# main.net
KiCad netlist of a schematic drawn in Altium Designer
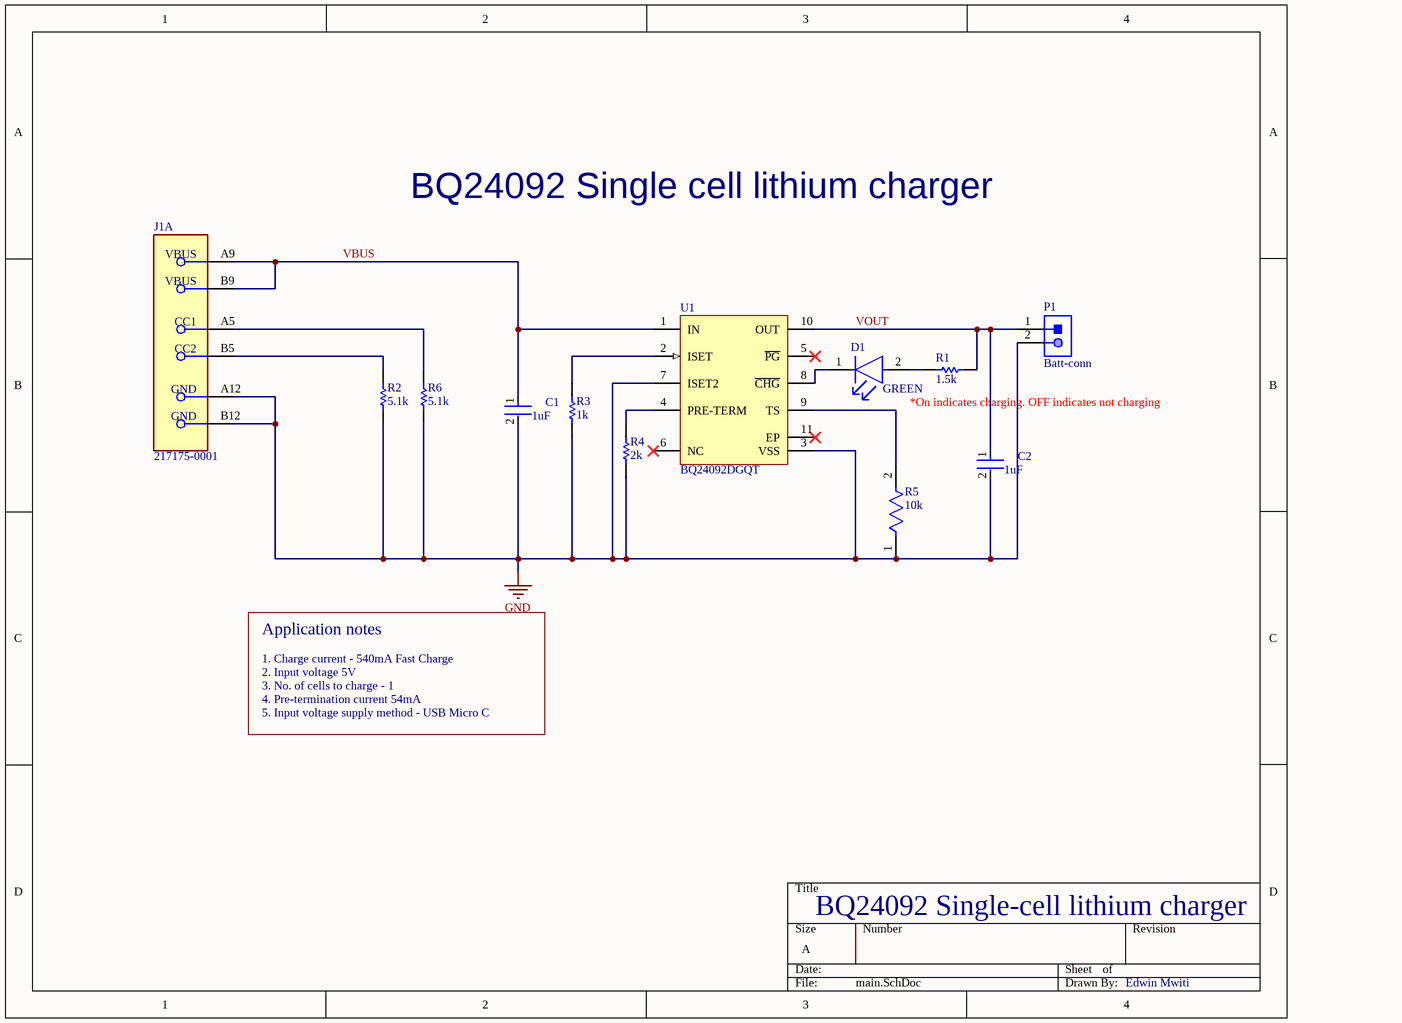
[diagram p0: main.SchDoc]

(export (version "E")
  (design (tool "Eeschema 10.0.6"))
  (components
    (comp (ref "C1")
      (value "1uF")
      (footprint "FP-CC0805-0_85-MFG")
      (description "CAP CER 1UF 16V X7R 0805")
      (fields
        (field (name "MANUFACTURER") "Yageo")
        (field (name "OCTOPART") "https://octopart.com/cc0805kkx7r7bb105-yageo-8376555")
      )
      (libsource (lib "Altium Content Vault") (part "11868f565c42a9108669ba33697ecf6"))
    )
    (comp (ref "C2")
      (value "1uF")
      (footprint "FP-CC0805-0_85-MFG")
      (description "CAP CER 1UF 16V X7R 0805")
      (fields
        (field (name "MANUFACTURER") "Yageo")
        (field (name "OCTOPART") "https://octopart.com/cc0805kkx7r7bb105-yageo-8376555")
      )
      (libsource (lib "Altium Content Vault") (part "11868f565c42a9108669ba33697ecf6"))
    )
    (comp (ref "D1")
      (value "GREEN")
      (footprint "FP-SML-210-MFG")
      (description "LED GREEN CLEAR 0805 SMD")
      (fields (field (name "MANUFACTURER PART NUMBER") "SML-210MTT86") (field (name "MANUFACTURER") "ROHM"))
      (libsource (lib "Altium Content Vault") (part "8706943c75ba83719d021d2fdc84c58"))
    )
    (comp (ref "J1")
      (value "217175-0001")
      (footprint "FP-217175-0001-MFG")
      (description "CONN RCP USB2.0 C 6+18P SMD RA")
      (libsource (lib "Altium Content Vault") (part "6a66c69350f09309f94811689c98437"))
    )
    (comp (ref "P1")
      (value "Batt-conn")
      (footprint "JST-S2B-PH-K-S_V")
      (fields (field (name "TOLERANCE") "20%"))
      (libsource (lib "Altium Content Vault") (part "CN-1P-M-R2"))
    )
    (comp (ref "R1")
      (value "1.5k")
      (footprint "RESC2013X60X40ML20T25")
      (fields (field (name "MANUFACTURER") "Panasonic") (field (name "PART NUMBER") "ERA6AEB152V"))
      (libsource (lib "Altium Content Vault") (part "RES"))
    )
    (comp (ref "R2")
      (value "5.1k")
      (footprint "RESC2013X70X40LL20T20")
      (fields (field (name "MANUFACTURER") "Panasonic") (field (name "PART NUMBER") "ERJ-6GEYJ512V"))
      (libsource (lib "Altium Content Vault") (part "RES"))
    )
    (comp (ref "R3")
      (value "1k")
      (footprint "RESC2013X70X40ML20T20")
      (description "Chip Resistor, 1 KOhm, +/- 1%, 0.125 W, -55 to 155 degC, 0805 (2012 Metric), RoHS, Tape and Reel")
      (fields (field (name "MANUFACTURER") "Panasonic"))
      (libsource (lib "Altium Content Vault") (part "RES-2"))
    )
    (comp (ref "R4")
      (value "2k")
      (footprint "RESC2013X60X35LL10T20")
      (fields (field (name "MANUFACTURER") "Yageo") (field (name "PART NUMBER") "RC0805JR-072KL"))
      (libsource (lib "Altium Content Vault") (part "RES"))
    )
    (comp (ref "R5")
      (value "10k")
      (footprint "FP-CRCW0805-e3-IPC_A")
      (description "RES Thick Film, 10kΩ, 1%, 0.125W, 100ppm/°C, 0805")
      (fields (field (name "TOLERANCE") "1%"))
      (libsource (lib "Altium Content Vault") (part "1029c3af85768c4190bb7ad29bc67b5"))
    )
    (comp (ref "R6")
      (value "5.1k")
      (footprint "RESC2013X70X40LL20T20")
      (fields (field (name "MANUFACTURER") "Panasonic") (field (name "PART NUMBER") "ERJ-6GEYJ512V"))
      (libsource (lib "Altium Content Vault") (part "RES"))
    )
    (comp (ref "U1")
      (value "BQ24092DGQT")
      (footprint "DGQ0010D_M")
      (fields (field (name "MANUFACTURER") "Texas Instruments"))
      (libsource (lib "Altium Content Vault") (part "TI-BQ24092DGQ10-1675X1445TP"))
    )
  )
  (nets
    (net (code "1") (name "/VBUS") (class "Default")
      (node (ref "C1") (pin "1") (pinfunction "1_1") (pintype "passive"))
      (node (ref "J1") (pin "A9") (pinfunction "VBUS_A9") (pintype "power_in"))
      (node (ref "J1") (pin "B9") (pinfunction "VBUS_B9") (pintype "power_in"))
      (node (ref "U1") (pin "1") (pinfunction "IN_1") (pintype "power_in"))
    )
    (net (code "2") (name "/VOUT") (class "Default")
      (node (ref "C2") (pin "1") (pinfunction "1_1") (pintype "passive"))
      (node (ref "P1") (pin "1") (pinfunction "1_1") (pintype "passive"))
      (node (ref "R1") (pin "1") (pinfunction "1_1") (pintype "passive"))
      (node (ref "U1") (pin "10") (pinfunction "OUT_10") (pintype "power_in"))
    )
    (net (code "3") (name "GND") (class "Default")
      (node (ref "C1") (pin "2") (pinfunction "2_2") (pintype "passive"))
      (node (ref "C2") (pin "2") (pinfunction "2_2") (pintype "passive"))
      (node (ref "J1") (pin "A12") (pinfunction "GND_A12") (pintype "power_in"))
      (node (ref "J1") (pin "B12") (pinfunction "GND_B12") (pintype "power_in"))
      (node (ref "P1") (pin "2") (pinfunction "2_2") (pintype "passive"))
      (node (ref "R2") (pin "1") (pinfunction "1_1") (pintype "passive"))
      (node (ref "R3") (pin "1") (pinfunction "1_1") (pintype "passive"))
      (node (ref "R4") (pin "1") (pinfunction "1_1") (pintype "passive"))
      (node (ref "R5") (pin "1") (pinfunction "1_1") (pintype "passive"))
      (node (ref "R6") (pin "1") (pinfunction "1_1") (pintype "passive"))
      (node (ref "U1") (pin "3") (pinfunction "VSS_3") (pintype "power_in"))
      (node (ref "U1") (pin "7") (pinfunction "ISET2_7") (pintype "passive"))
    )
    (net (code "4") (name "Net-(D1-A)") (class "Default")
      (node (ref "D1") (pin "2") (pinfunction "A_2") (pintype "passive"))
      (node (ref "R1") (pin "2") (pinfunction "2_2") (pintype "passive"))
    )
    (net (code "5") (name "Net-(D1-C)") (class "Default")
      (node (ref "D1") (pin "1") (pinfunction "C_1") (pintype "passive"))
      (node (ref "U1") (pin "8") (pinfunction "~{CHG}_8") (pintype "tri_state"))
    )
    (net (code "6") (name "Net-(J1A-CC1)") (class "Default")
      (node (ref "J1") (pin "A5") (pinfunction "CC1_A5") (pintype "passive"))
      (node (ref "R6") (pin "2") (pinfunction "2_2") (pintype "passive"))
    )
    (net (code "7") (name "Net-(J1A-CC2)") (class "Default")
      (node (ref "J1") (pin "B5") (pinfunction "CC2_B5") (pintype "passive"))
      (node (ref "R2") (pin "2") (pinfunction "2_2") (pintype "passive"))
    )
    (net (code "8") (name "Net-(U1-ISET)") (class "Default")
      (node (ref "R3") (pin "2") (pinfunction "2_2") (pintype "passive"))
      (node (ref "U1") (pin "2") (pinfunction "ISET_2") (pintype "input"))
    )
    (net (code "9") (name "Net-(U1-PRE-TERM)") (class "Default")
      (node (ref "R4") (pin "2") (pinfunction "2_2") (pintype "passive"))
      (node (ref "U1") (pin "4") (pinfunction "PRE-TERM_4") (pintype "passive"))
    )
    (net (code "10") (name "Net-(U1-TS)") (class "Default")
      (node (ref "R5") (pin "2") (pinfunction "2_2") (pintype "passive"))
      (node (ref "U1") (pin "9") (pinfunction "TS_9") (pintype "passive"))
    )
    (net (code "11") (name "unconnected-(U1-EP-Pad11)") (class "Default")
      (node (ref "U1") (pin "11") (pinfunction "EP_11") (pintype "power_in+no_connect"))
    )
    (net (code "12") (name "unconnected-(U1-NC-Pad6)") (class "Default")
      (node (ref "U1") (pin "6") (pinfunction "NC_6") (pintype "passive+no_connect"))
    )
    (net (code "13") (name "unconnected-(U1-~{PG}-Pad5)") (class "Default")
      (node (ref "U1") (pin "5") (pinfunction "~{PG}_5") (pintype "tri_state+no_connect"))
    )
  )
)
